# PLWD_LTE_stmod.net
KiCad netlist of a schematic drawn in Altium Designer
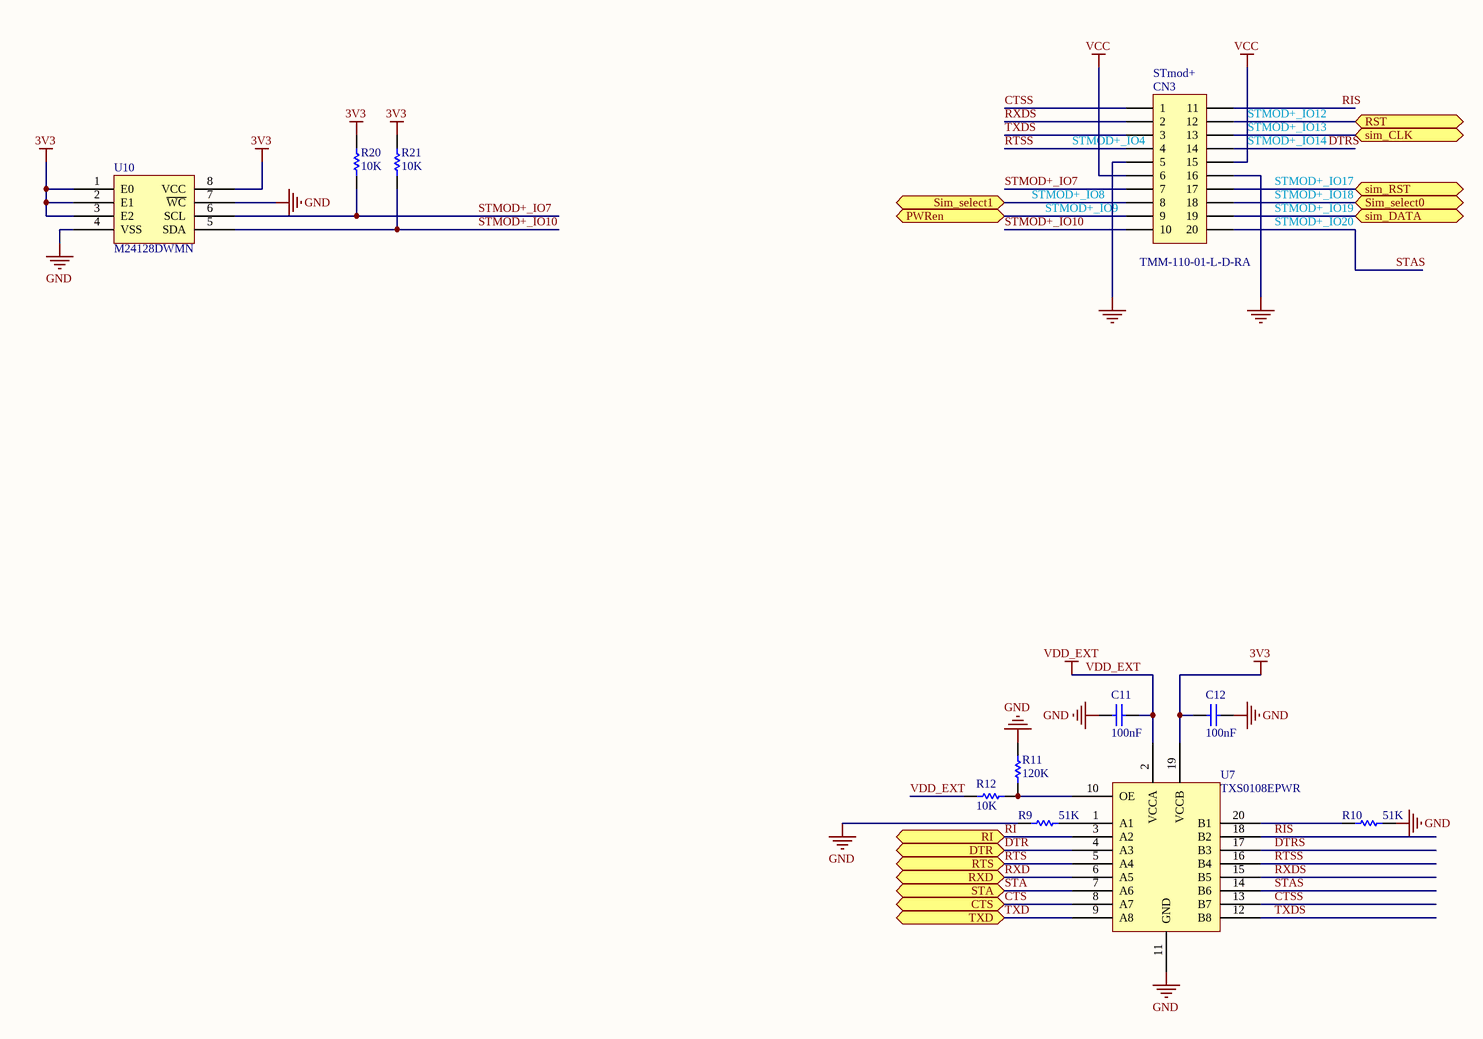
[diagram p0: PLWD_LTE_stmod.SchDoc]

(export (version "E")
  (design (tool "Eeschema 10.0.6"))
  (components
    (comp (ref "C11")
      (value "100nF")
      (footprint "C0402")
      (description "Capacitor,100nF,16V,X7R,10%,0402,YAGEO")
      (fields
        (field (name "INTERNAL_PART_NUMBER") "MCD-00006")
        (field (name "MANUFACTURER_PART_NUMBER") "CC0402KRX7R7BB104")
        (field (name "PROVIDED_BY") "Subcon")
      )
      (libsource (lib "MCD_PARTS_database") (part "Capacitor"))
    )
    (comp (ref "C12")
      (value "100nF")
      (footprint "C0402")
      (description "Capacitor,100nF,16V,X7R,10%,0402,YAGEO")
      (fields
        (field (name "INTERNAL_PART_NUMBER") "MCD-00006")
        (field (name "MANUFACTURER_PART_NUMBER") "CC0402KRX7R7BB104")
        (field (name "PROVIDED_BY") "Subcon")
      )
      (libsource (lib "MCD_PARTS_database") (part "Capacitor"))
    )
    (comp (ref "CN3")
      (value "TMM-110-01-L-D-RA")
      (footprint "CON_SAMTEC_TMM-110-01-L-D-RA__STMOD+")
      (description "Header 20 pins 2 row")
      (fields
        (field (name "INTERNAL_PART_NUMBER") "MCD-00288")
        (field (name "MANUFACTURER") "SAMTEC")
        (field (name "PROVIDED_BY") "SubCon")
      )
      (libsource (lib "MCD_PARTS_database") (part "TMM-110-01-L-D-RA"))
    )
    (comp (ref "R9")
      (value "51K")
      (footprint "R0402")
      (description "Resistor,51K,0402,1%,YAGEO")
      (fields
        (field (name "INTERNAL_PART_NUMBER") "MCD-00294")
        (field (name "MANUFACTURER_PART_NUMBER") "RC0402FR-0751KL")
        (field (name "PROVIDED_BY") "Subcon")
      )
      (libsource (lib "MCD_PARTS_database") (part "Resistor"))
    )
    (comp (ref "R10")
      (value "51K")
      (footprint "R0402")
      (description "Resistor,51K,0402,1%,YAGEO")
      (fields
        (field (name "INTERNAL_PART_NUMBER") "MCD-00294")
        (field (name "MANUFACTURER_PART_NUMBER") "RC0402FR-0751KL")
        (field (name "PROVIDED_BY") "Subcon")
      )
      (libsource (lib "MCD_PARTS_database") (part "Resistor"))
    )
    (comp (ref "R11")
      (value "120K")
      (footprint "R0402")
      (description "Resistor,120K,0402,1%,YAGEO")
      (fields
        (field (name "INTERNAL_PART_NUMBER") "MCD-00166")
        (field (name "MANUFACTURER_PART_NUMBER") "RC0402FR-07120KL")
        (field (name "PROVIDED_BY") "Subcon")
      )
      (libsource (lib "MCD_PARTS_database") (part "Resistor"))
    )
    (comp (ref "R12")
      (value "10K")
      (footprint "R0603")
      (description "Resistor,10K,0603,1%,YAGEO")
      (fields
        (field (name "INTERNAL_PART_NUMBER") "MCD-00220")
        (field (name "MANUFACTURER_PART_NUMBER") "RC0603FR-0710KL")
        (field (name "PROVIDED_BY") "Subcon")
      )
      (libsource (lib "MCD_PARTS_database") (part "Resistor"))
    )
    (comp (ref "R20")
      (value "10K")
      (footprint "R0402")
      (description "Resistor,10K,0402,1%")
      (fields
        (field (name "INTERNAL_PART_NUMBER") "MCD-00053")
        (field (name "MANUFACTURER_PART_NUMBER") "RC0402FR-0710KL")
        (field (name "PROVIDED_BY") "subcon")
      )
      (libsource (lib "MCD_PARTS_database") (part "Resistor"))
    )
    (comp (ref "R21")
      (value "10K")
      (footprint "R0402")
      (description "Resistor,10K,0402,1%")
      (fields
        (field (name "INTERNAL_PART_NUMBER") "MCD-00053")
        (field (name "MANUFACTURER_PART_NUMBER") "RC0402FR-0710KL")
        (field (name "PROVIDED_BY") "subcon")
      )
      (libsource (lib "MCD_PARTS_database") (part "Resistor"))
    )
    (comp (ref "U7")
      (value "TXS0108EPWR")
      (footprint "ICC_TSSOP20_6P50X4P40_P065")
      (description "bidirectionnal level shifter")
      (fields
        (field (name "INTERNAL_PART_NUMBER") "MCD-00289")
        (field (name "MANUFACTURER") "TEXAS INSTRUMENTS")
        (field (name "PROVIDED_BY") "Subcon")
      )
      (libsource (lib "MCD_PARTS_database") (part "TXS0108EPWR"))
    )
    (comp (ref "U10")
      (value "M24128DWMN")
      (footprint "ICC_SO8_5X4_P127")
      (description "I2C memory")
      (fields (field (name "INTERNAL_PART_NUMBER") "MCD-00293") (field (name "MANUFACTURER") "ST"))
      (libsource (lib "MCD_PARTS_database") (part "M24128DWMN"))
    )
  )
  (nets
    (net (code "1") (name "/CTS") (class "Default")
      (node (ref "U7") (pin "8") (pinfunction "A7_8") (pintype "passive"))
    )
    (net (code "2") (name "/CTSS") (class "Default")
      (node (ref "CN3") (pin "1") (pinfunction "1_1") (pintype "passive"))
      (node (ref "U7") (pin "13") (pinfunction "B7_13") (pintype "passive"))
    )
    (net (code "3") (name "/DTR") (class "Default")
      (node (ref "U7") (pin "4") (pinfunction "A3_4") (pintype "passive"))
    )
    (net (code "4") (name "/DTRS") (class "Default")
      (node (ref "CN3") (pin "14") (pinfunction "14_14") (pintype "passive"))
      (node (ref "U7") (pin "17") (pinfunction "B3_17") (pintype "passive"))
    )
    (net (code "5") (name "/PWRen") (class "Default")
      (node (ref "CN3") (pin "9") (pinfunction "9_9") (pintype "passive"))
    )
    (net (code "6") (name "/RI") (class "Default")
      (node (ref "U7") (pin "3") (pinfunction "A2_3") (pintype "passive"))
    )
    (net (code "7") (name "/RIS") (class "Default")
      (node (ref "CN3") (pin "11") (pinfunction "11_11") (pintype "passive"))
      (node (ref "U7") (pin "18") (pinfunction "B2_18") (pintype "passive"))
    )
    (net (code "8") (name "/RST") (class "Default")
      (node (ref "CN3") (pin "12") (pinfunction "12_12") (pintype "passive"))
    )
    (net (code "9") (name "/RTS") (class "Default")
      (node (ref "U7") (pin "5") (pinfunction "A4_5") (pintype "passive"))
    )
    (net (code "10") (name "/RTSS") (class "Default")
      (node (ref "CN3") (pin "4") (pinfunction "4_4") (pintype "passive"))
      (node (ref "U7") (pin "16") (pinfunction "B4_16") (pintype "passive"))
    )
    (net (code "11") (name "/RXD") (class "Default")
      (node (ref "U7") (pin "6") (pinfunction "A5_6") (pintype "passive"))
    )
    (net (code "12") (name "/RXDS") (class "Default")
      (node (ref "CN3") (pin "2") (pinfunction "2_2") (pintype "passive"))
      (node (ref "U7") (pin "15") (pinfunction "B5_15") (pintype "passive"))
    )
    (net (code "13") (name "/STA") (class "Default")
      (node (ref "U7") (pin "7") (pinfunction "A6_7") (pintype "passive"))
    )
    (net (code "14") (name "/STAS") (class "Default")
      (node (ref "CN3") (pin "20") (pinfunction "20_20") (pintype "passive"))
      (node (ref "U7") (pin "14") (pinfunction "B6_14") (pintype "passive"))
    )
    (net (code "15") (name "/STMOD+_IO7") (class "Default")
      (node (ref "CN3") (pin "7") (pinfunction "7_7") (pintype "passive"))
      (node (ref "R20") (pin "1") (pinfunction "1_1") (pintype "passive"))
      (node (ref "U10") (pin "6") (pinfunction "SCL_6") (pintype "passive"))
    )
    (net (code "16") (name "/STMOD+_IO10") (class "Default")
      (node (ref "CN3") (pin "10") (pinfunction "10_10") (pintype "passive"))
      (node (ref "R21") (pin "1") (pinfunction "1_1") (pintype "passive"))
      (node (ref "U10") (pin "5") (pinfunction "SDA_5") (pintype "passive"))
    )
    (net (code "17") (name "/Sim_select0") (class "Default")
      (node (ref "CN3") (pin "18") (pinfunction "18_18") (pintype "passive"))
    )
    (net (code "18") (name "/Sim_select1") (class "Default")
      (node (ref "CN3") (pin "8") (pinfunction "8_8") (pintype "passive"))
    )
    (net (code "19") (name "/TXD") (class "Default")
      (node (ref "U7") (pin "9") (pinfunction "A8_9") (pintype "passive"))
    )
    (net (code "20") (name "/TXDS") (class "Default")
      (node (ref "CN3") (pin "3") (pinfunction "3_3") (pintype "passive"))
      (node (ref "U7") (pin "12") (pinfunction "B8_12") (pintype "passive"))
    )
    (net (code "21") (name "/sim_CLK") (class "Default")
      (node (ref "CN3") (pin "13") (pinfunction "13_13") (pintype "passive"))
    )
    (net (code "22") (name "/sim_DATA") (class "Default")
      (node (ref "CN3") (pin "19") (pinfunction "19_19") (pintype "passive"))
    )
    (net (code "23") (name "/sim_RST") (class "Default")
      (node (ref "CN3") (pin "17") (pinfunction "17_17") (pintype "passive"))
    )
    (net (code "24") (name "3V3") (class "Default")
      (node (ref "C12") (pin "1") (pinfunction "1_1") (pintype "passive"))
      (node (ref "R20") (pin "2") (pinfunction "2_2") (pintype "passive"))
      (node (ref "R21") (pin "2") (pinfunction "2_2") (pintype "passive"))
      (node (ref "U10") (pin "1") (pinfunction "E0_1") (pintype "passive"))
      (node (ref "U10") (pin "2") (pinfunction "E1_2") (pintype "passive"))
      (node (ref "U10") (pin "3") (pinfunction "E2_3") (pintype "passive"))
      (node (ref "U10") (pin "8") (pinfunction "VCC_8") (pintype "passive"))
      (node (ref "U7") (pin "19") (pinfunction "VCCB_19") (pintype "passive"))
    )
    (net (code "25") (name "GND") (class "Default")
      (node (ref "C11") (pin "1") (pinfunction "1_1") (pintype "passive"))
      (node (ref "C12") (pin "2") (pinfunction "2_2") (pintype "passive"))
      (node (ref "CN3") (pin "16") (pinfunction "16_16") (pintype "passive"))
      (node (ref "CN3") (pin "5") (pinfunction "5_5") (pintype "passive"))
      (node (ref "R10") (pin "2") (pinfunction "2_2") (pintype "passive"))
      (node (ref "R11") (pin "2") (pinfunction "2_2") (pintype "passive"))
      (node (ref "R9") (pin "1") (pinfunction "1_1") (pintype "passive"))
      (node (ref "U10") (pin "4") (pinfunction "VSS_4") (pintype "passive"))
      (node (ref "U10") (pin "7") (pinfunction "~{WC}_7") (pintype "passive"))
      (node (ref "U7") (pin "11") (pinfunction "GND_11") (pintype "passive"))
    )
    (net (code "26") (name "Net-(U7-A1)") (class "Default")
      (node (ref "R9") (pin "2") (pinfunction "2_2") (pintype "passive"))
      (node (ref "U7") (pin "1") (pinfunction "A1_1") (pintype "passive"))
    )
    (net (code "27") (name "Net-(U7-B1)") (class "Default")
      (node (ref "R10") (pin "1") (pinfunction "1_1") (pintype "passive"))
      (node (ref "U7") (pin "20") (pinfunction "B1_20") (pintype "passive"))
    )
    (net (code "28") (name "Net-(U7-OE)") (class "Default")
      (node (ref "R11") (pin "1") (pinfunction "1_1") (pintype "passive"))
      (node (ref "R12") (pin "2") (pinfunction "2_2") (pintype "passive"))
      (node (ref "U7") (pin "10") (pinfunction "OE_10") (pintype "passive"))
    )
    (net (code "29") (name "VCC") (class "Default")
      (node (ref "CN3") (pin "15") (pinfunction "15_15") (pintype "passive"))
      (node (ref "CN3") (pin "6") (pinfunction "6_6") (pintype "passive"))
    )
    (net (code "30") (name "VDD_EXT") (class "Default")
      (node (ref "C11") (pin "2") (pinfunction "2_2") (pintype "passive"))
      (node (ref "R12") (pin "1") (pinfunction "1_1") (pintype "passive"))
      (node (ref "U7") (pin "2") (pinfunction "VCCA_2") (pintype "passive"))
    )
  )
)
